# MultiDrop.net
KiCad netlist of a schematic drawn in EAGLE
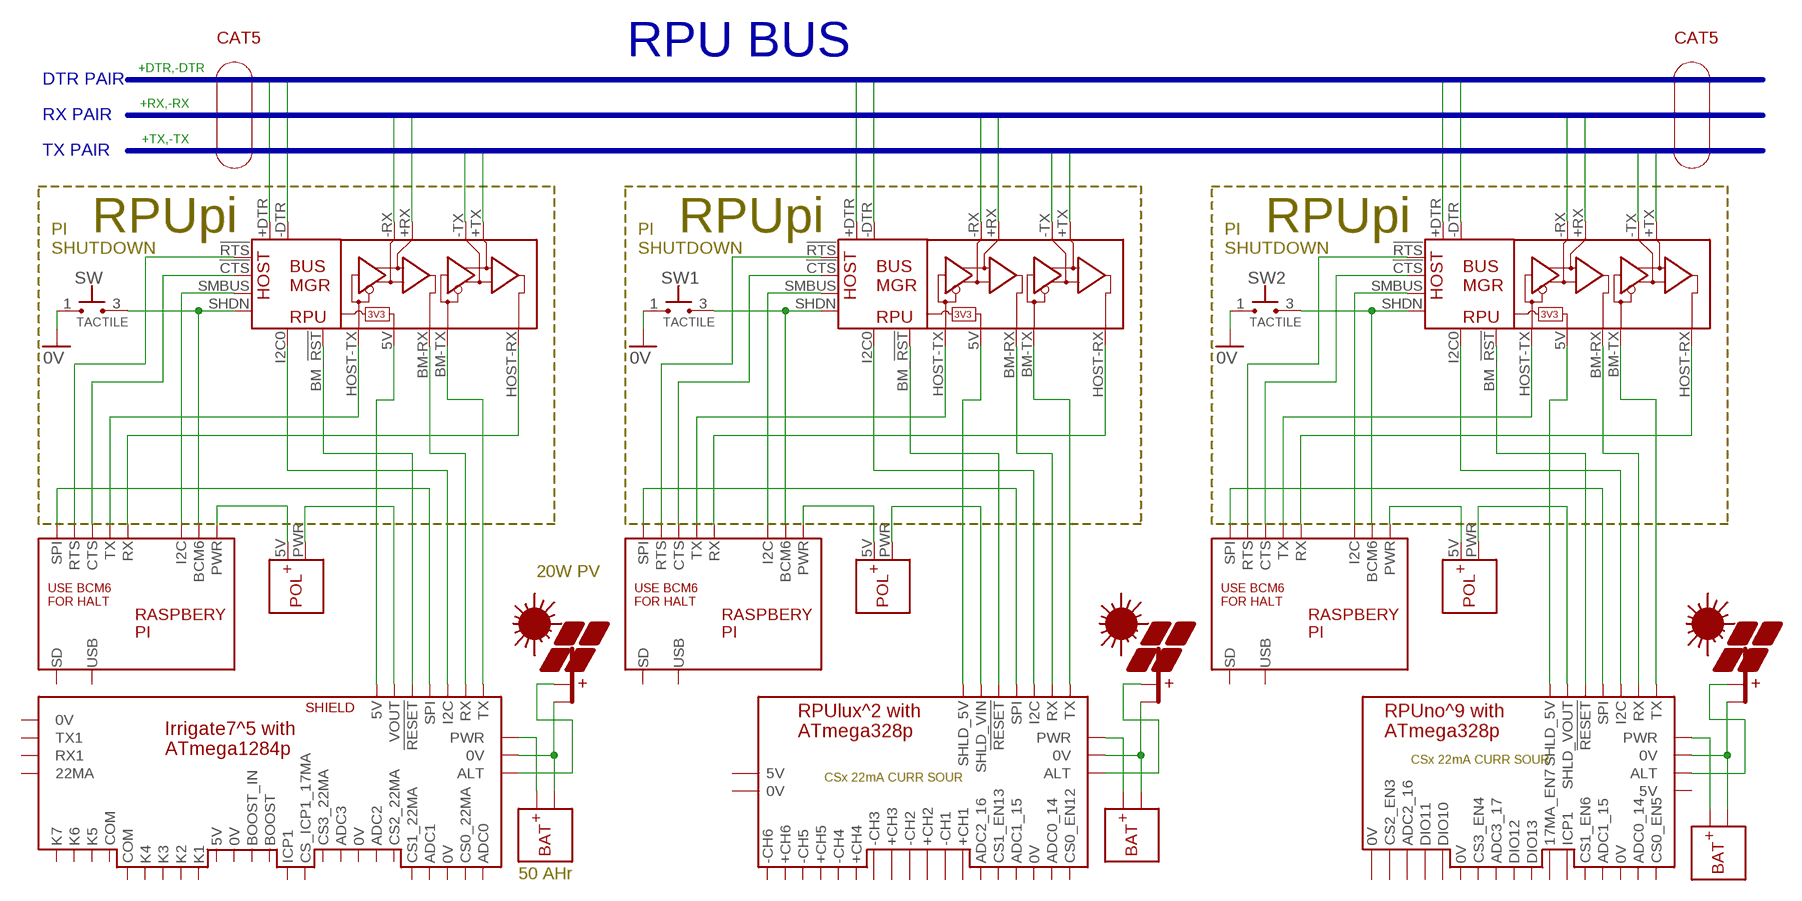
[diagram p0: schematic, sheet 1]

(export (version "E")
  (design (tool "Eeschema 10.0.6"))
  (components
    (comp (ref "BM1")
      (value "RPUNO")
      (footprint "eagle-import:NA-30")
      (libsource (lib "eagle-import") (part "RPUNO"))
    )
    (comp (ref "PV1")
      (value "PV")
      (footprint "eagle-import:NA-30")
      (libsource (lib "eagle-import") (part "PV"))
    )
    (comp (ref "PV2")
      (value "PV")
      (footprint "eagle-import:NA-30")
      (libsource (lib "eagle-import") (part "PV"))
    )
    (comp (ref "PV4")
      (value "PV")
      (footprint "eagle-import:NA-30")
      (libsource (lib "eagle-import") (part "PV"))
    )
    (comp (ref "SW")
      (value "TACTILE")
      (footprint "eagle-import:KS11")
      (libsource (lib "eagle-import") (part "TAC_SW"))
    )
    (comp (ref "SW1")
      (value "TACTILE")
      (footprint "eagle-import:KS11")
      (libsource (lib "eagle-import") (part "TAC_SW"))
    )
    (comp (ref "SW2")
      (value "TACTILE")
      (footprint "eagle-import:KS11")
      (libsource (lib "eagle-import") (part "TAC_SW"))
    )
    (comp (ref "U$1")
      (value "IRRIGATE7")
      (footprint "eagle-import:WITH_RPU_NAMES")
      (libsource (lib "eagle-import") (part "IRRIGATE7"))
    )
    (comp (ref "U$2")
      (value "RPULUX")
      (footprint "eagle-import:WITH_RPU_NAMES")
      (libsource (lib "eagle-import") (part "RPULUX"))
    )
    (comp (ref "U$3")
      (value "BUS_MGR")
      (footprint "eagle-import:WITH_RPU_NAMES")
      (libsource (lib "eagle-import") (part "BUS_MGR"))
    )
    (comp (ref "U$4")
      (value "BAT")
      (footprint "eagle-import:NA-30")
      (libsource (lib "eagle-import") (part "BAT"))
    )
    (comp (ref "U$5")
      (value "PI")
      (footprint "eagle-import:NA-30")
      (libsource (lib "eagle-import") (part "PI"))
    )
    (comp (ref "U$6")
      (value "BUS_MGR")
      (footprint "eagle-import:WITH_RPU_NAMES")
      (libsource (lib "eagle-import") (part "BUS_MGR"))
    )
    (comp (ref "U$7")
      (value "BAT")
      (footprint "eagle-import:NA-30")
      (libsource (lib "eagle-import") (part "BAT"))
    )
    (comp (ref "U$8")
      (value "BUS_MGR")
      (footprint "eagle-import:WITH_RPU_NAMES")
      (libsource (lib "eagle-import") (part "BUS_MGR"))
    )
    (comp (ref "U$9")
      (value "BAT")
      (footprint "eagle-import:NA-30")
      (libsource (lib "eagle-import") (part "BAT"))
    )
    (comp (ref "U$10")
      (value "PI")
      (footprint "eagle-import:NA-30")
      (libsource (lib "eagle-import") (part "PI"))
    )
    (comp (ref "U$11")
      (value "PI")
      (footprint "eagle-import:NA-30")
      (libsource (lib "eagle-import") (part "PI"))
    )
    (comp (ref "U$12")
      (value "POL")
      (footprint "eagle-import:WITH_RPU_NAMES")
      (libsource (lib "eagle-import") (part "POL"))
    )
    (comp (ref "U$13")
      (value "POL")
      (footprint "eagle-import:WITH_RPU_NAMES")
      (libsource (lib "eagle-import") (part "POL"))
    )
    (comp (ref "U$14")
      (value "POL")
      (footprint "eagle-import:WITH_RPU_NAMES")
      (libsource (lib "eagle-import") (part "POL"))
    )
  )
  (nets
    (net (code "10") (name "0V") (class "Default")
      (node (ref "SW") (pin "1") (pinfunction "1_1") (pintype "passive"))
      (node (ref "SW1") (pin "1") (pinfunction "1_1") (pintype "passive"))
      (node (ref "SW2") (pin "1") (pinfunction "1_1") (pintype "passive"))
    )
    (net (code "11") (name "Net-(BM1-ALT)") (class "Default")
      (node (ref "BM1") (pin "20") (pinfunction "ALT_20") (pintype "bidirectional"))
      (node (ref "PV4") (pin "1") (pinfunction "+PV_1") (pintype "bidirectional"))
    )
    (net (code "12") (name "Net-(BM1-I2C)") (class "Default")
      (node (ref "BM1") (pin "3") (pinfunction "I2C_3") (pintype "bidirectional"))
      (node (ref "U$6") (pin "I2C0") (pinfunction "I2C0_I2C0") (pintype "bidirectional"))
    )
    (net (code "13") (name "Net-(BM1-PWR)") (class "Default")
      (node (ref "BM1") (pin "8") (pinfunction "PWR_8") (pintype "bidirectional"))
      (node (ref "U$7") (pin "1") (pinfunction "+BAT_1") (pintype "bidirectional"))
    )
    (net (code "14") (name "Net-(BM1-RX)") (class "Default")
      (node (ref "BM1") (pin "2") (pinfunction "RX_2") (pintype "bidirectional"))
      (node (ref "U$6") (pin "BM-RX") (pinfunction "BM_RX_BM-RX") (pintype "bidirectional"))
    )
    (net (code "15") (name "Net-(BM1-SHLD_5V)") (class "Default")
      (node (ref "BM1") (pin "6") (pinfunction "SHLD_5V_6") (pintype "bidirectional"))
      (node (ref "U$6") (pin "5V") (pinfunction "PWR_5V") (pintype "bidirectional"))
    )
    (net (code "16") (name "Net-(BM1-SHLD_VOUT)") (class "Default")
      (node (ref "BM1") (pin "7") (pinfunction "SHLD_VOUT_7") (pintype "bidirectional"))
      (node (ref "U$14") (pin "PWR") (pinfunction "VIN_PWR") (pintype "bidirectional"))
    )
    (net (code "17") (name "Net-(BM1-SPI)") (class "Default")
      (node (ref "BM1") (pin "4") (pinfunction "SPI_4") (pintype "bidirectional"))
      (node (ref "U$10") (pin "10") (pinfunction "SPI_10") (pintype "bidirectional"))
    )
    (net (code "18") (name "Net-(BM1-TX)") (class "Default")
      (node (ref "BM1") (pin "1") (pinfunction "TX_1") (pintype "bidirectional"))
      (node (ref "U$6") (pin "BM-TX") (pinfunction "BM_TX_BM-TX") (pintype "bidirectional"))
    )
    (net (code "19") (name "Net-(BM1-~{RESET})") (class "Default")
      (node (ref "BM1") (pin "5") (pinfunction "~{RESET}_5") (pintype "bidirectional"))
      (node (ref "U$6") (pin "BM_!RST!") (pinfunction "BM-~{RST}_BM_!RST!") (pintype "bidirectional"))
    )
    (net (code "20") (name "Net-(PV1-+PV)") (class "Default")
      (node (ref "PV1") (pin "1") (pinfunction "+PV_1") (pintype "bidirectional"))
      (node (ref "U$1") (pin "AUX") (pinfunction "ALT_AUX") (pintype "bidirectional"))
    )
    (net (code "21") (name "Net-(PV1--PV)") (class "Default")
      (node (ref "PV1") (pin "2") (pinfunction "-PV_2") (pintype "bidirectional"))
      (node (ref "U$1") (pin "0V@PWR") (pinfunction "0V_0V@PWR") (pintype "bidirectional"))
      (node (ref "U$4") (pin "2") (pinfunction "-BAT_2") (pintype "bidirectional"))
    )
    (net (code "22") (name "Net-(PV2-+PV)") (class "Default")
      (node (ref "PV2") (pin "1") (pinfunction "+PV_1") (pintype "bidirectional"))
      (node (ref "U$2") (pin "AUX") (pinfunction "ALT_AUX") (pintype "bidirectional"))
    )
    (net (code "23") (name "Net-(PV2--PV)") (class "Default")
      (node (ref "PV2") (pin "2") (pinfunction "-PV_2") (pintype "bidirectional"))
      (node (ref "U$2") (pin "0V@PWR") (pinfunction "0V_0V@PWR") (pintype "bidirectional"))
      (node (ref "U$9") (pin "2") (pinfunction "-BAT_2") (pintype "bidirectional"))
    )
    (net (code "24") (name "Net-(PV4--PV)") (class "Default")
      (node (ref "BM1") (pin "9") (pinfunction "0V_9") (pintype "bidirectional"))
      (node (ref "PV4") (pin "2") (pinfunction "-PV_2") (pintype "bidirectional"))
      (node (ref "U$7") (pin "2") (pinfunction "-BAT_2") (pintype "bidirectional"))
    )
    (net (code "25") (name "Net-(U$1-PadI2C)") (class "Default")
      (node (ref "U$1") (pin "I2C") (pinfunction "I2C_I2C") (pintype "bidirectional"))
      (node (ref "U$8") (pin "I2C0") (pinfunction "I2C0_I2C0") (pintype "bidirectional"))
    )
    (net (code "26") (name "Net-(U$1-VOUT)") (class "Default")
      (node (ref "U$1") (pin "SHLD_VOUT") (pinfunction "VOUT_SHLD_VOUT") (pintype "bidirectional"))
      (node (ref "U$12") (pin "PWR") (pinfunction "VIN_PWR") (pintype "bidirectional"))
    )
    (net (code "27") (name "Net-(U$1-~{RESET})") (class "Default")
      (node (ref "U$1") (pin "!RESET") (pinfunction "~{RESET}_!RESET") (pintype "bidirectional"))
      (node (ref "U$8") (pin "BM_!RST!") (pinfunction "BM-~{RST}_BM_!RST!") (pintype "bidirectional"))
    )
    (net (code "28") (name "Net-(U$2-PadI2C)") (class "Default")
      (node (ref "U$2") (pin "I2C") (pinfunction "I2C_I2C") (pintype "bidirectional"))
      (node (ref "U$3") (pin "I2C0") (pinfunction "I2C0_I2C0") (pintype "bidirectional"))
    )
    (net (code "29") (name "Net-(U$2-~{RESET})") (class "Default")
      (node (ref "U$2") (pin "!RESET") (pinfunction "~{RESET}_!RESET") (pintype "bidirectional"))
      (node (ref "U$3") (pin "BM_!RST!") (pinfunction "BM-~{RST}_BM_!RST!") (pintype "bidirectional"))
    )
    (net (code "30") (name "Net-(U$3-BM_RX)") (class "Default")
      (node (ref "U$2") (pin "RX") (pinfunction "RX_RX") (pintype "bidirectional"))
      (node (ref "U$3") (pin "BM-RX") (pinfunction "BM_RX_BM-RX") (pintype "bidirectional"))
    )
    (net (code "31") (name "Net-(U$3-BM_TX)") (class "Default")
      (node (ref "U$2") (pin "TX") (pinfunction "TX_TX") (pintype "bidirectional"))
      (node (ref "U$3") (pin "BM-TX") (pinfunction "BM_TX_BM-TX") (pintype "bidirectional"))
    )
    (net (code "32") (name "Net-(U$3-HOST_RX)") (class "Default")
      (node (ref "U$3") (pin "HOST-RX") (pinfunction "HOST_RX_HOST-RX") (pintype "bidirectional"))
      (node (ref "U$5") (pin "3") (pinfunction "RX_3") (pintype "bidirectional"))
    )
    (net (code "33") (name "Net-(U$3-HOST_TX)") (class "Default")
      (node (ref "U$3") (pin "HOST-TX") (pinfunction "HOST_TX_HOST-TX") (pintype "bidirectional"))
      (node (ref "U$5") (pin "4") (pinfunction "TX_4") (pintype "bidirectional"))
    )
    (net (code "34") (name "Net-(U$3-PWR)") (class "Default")
      (node (ref "U$2") (pin "SHLD_5V") (pinfunction "SHLD_5V_SHLD_5V") (pintype "bidirectional"))
      (node (ref "U$3") (pin "5V") (pinfunction "PWR_5V") (pintype "bidirectional"))
    )
    (net (code "35") (name "Net-(U$3-~{CTS})") (class "Default")
      (node (ref "U$3") (pin "!CTS") (pinfunction "~{CTS}_!CTS") (pintype "bidirectional"))
      (node (ref "U$5") (pin "1") (pinfunction "CTS_1") (pintype "input"))
    )
    (net (code "36") (name "Net-(U$3-~{RTS})") (class "Default")
      (node (ref "U$3") (pin "!RTS") (pinfunction "~{RTS}_!RTS") (pintype "bidirectional"))
      (node (ref "U$5") (pin "2") (pinfunction "RTS_2") (pintype "input"))
    )
    (net (code "37") (name "Net-(U$4-+BAT)") (class "Default")
      (node (ref "U$1") (pin "PWR") (pinfunction "PWR_PWR") (pintype "bidirectional"))
      (node (ref "U$4") (pin "1") (pinfunction "+BAT_1") (pintype "bidirectional"))
    )
    (net (code "38") (name "Net-(U$5-BCM6)") (class "Default")
      (node (ref "SW1") (pin "3") (pinfunction "3_3") (pintype "passive"))
      (node (ref "U$3") (pin "SHDN") (pinfunction "SHDN_SHDN") (pintype "bidirectional"))
      (node (ref "U$5") (pin "7") (pinfunction "BCM6_7") (pintype "bidirectional"))
    )
    (net (code "39") (name "Net-(U$5-I2C)") (class "Default")
      (node (ref "U$3") (pin "SMBUS") (pinfunction "SMBUS_SMBUS") (pintype "bidirectional"))
      (node (ref "U$5") (pin "8") (pinfunction "I2C_8") (pintype "bidirectional"))
    )
    (net (code "40") (name "Net-(U$5-PWR)") (class "Default")
      (node (ref "U$13") (pin "5V") (pinfunction "5V_5V") (pintype "bidirectional"))
      (node (ref "U$5") (pin "12") (pinfunction "PWR_12") (pintype "bidirectional"))
    )
    (net (code "41") (name "Net-(U$5-SPI)") (class "Default")
      (node (ref "U$2") (pin "SPI") (pinfunction "SPI_SPI") (pintype "bidirectional"))
      (node (ref "U$5") (pin "10") (pinfunction "SPI_10") (pintype "bidirectional"))
    )
    (net (code "42") (name "Net-(U$8-BM_RX)") (class "Default")
      (node (ref "U$1") (pin "RX") (pinfunction "RX_RX") (pintype "bidirectional"))
      (node (ref "U$8") (pin "BM-RX") (pinfunction "BM_RX_BM-RX") (pintype "bidirectional"))
    )
    (net (code "43") (name "Net-(U$8-BM_TX)") (class "Default")
      (node (ref "U$1") (pin "TX") (pinfunction "TX_TX") (pintype "bidirectional"))
      (node (ref "U$8") (pin "BM-TX") (pinfunction "BM_TX_BM-TX") (pintype "bidirectional"))
    )
    (net (code "44") (name "Net-(U$8-PWR)") (class "Default")
      (node (ref "U$1") (pin "SHLD_5V") (pinfunction "5V_SHLD_5V") (pintype "bidirectional"))
      (node (ref "U$8") (pin "5V") (pinfunction "PWR_5V") (pintype "bidirectional"))
    )
    (net (code "45") (name "Net-(U$9-+BAT)") (class "Default")
      (node (ref "U$2") (pin "PWR") (pinfunction "PWR_PWR") (pintype "bidirectional"))
      (node (ref "U$9") (pin "1") (pinfunction "+BAT_1") (pintype "bidirectional"))
    )
    (net (code "46") (name "Net-(U$10-BCM6)") (class "Default")
      (node (ref "SW2") (pin "3") (pinfunction "3_3") (pintype "passive"))
      (node (ref "U$10") (pin "7") (pinfunction "BCM6_7") (pintype "bidirectional"))
      (node (ref "U$6") (pin "SHDN") (pinfunction "SHDN_SHDN") (pintype "bidirectional"))
    )
    (net (code "47") (name "Net-(U$10-CTS)") (class "Default")
      (node (ref "U$10") (pin "1") (pinfunction "CTS_1") (pintype "input"))
      (node (ref "U$6") (pin "!CTS") (pinfunction "~{CTS}_!CTS") (pintype "bidirectional"))
    )
    (net (code "48") (name "Net-(U$10-I2C)") (class "Default")
      (node (ref "U$10") (pin "8") (pinfunction "I2C_8") (pintype "bidirectional"))
      (node (ref "U$6") (pin "SMBUS") (pinfunction "SMBUS_SMBUS") (pintype "bidirectional"))
    )
    (net (code "49") (name "Net-(U$10-PWR)") (class "Default")
      (node (ref "U$10") (pin "12") (pinfunction "PWR_12") (pintype "bidirectional"))
      (node (ref "U$14") (pin "5V") (pinfunction "5V_5V") (pintype "bidirectional"))
    )
    (net (code "50") (name "Net-(U$10-RTS)") (class "Default")
      (node (ref "U$10") (pin "2") (pinfunction "RTS_2") (pintype "input"))
      (node (ref "U$6") (pin "!RTS") (pinfunction "~{RTS}_!RTS") (pintype "bidirectional"))
    )
    (net (code "51") (name "Net-(U$10-RX)") (class "Default")
      (node (ref "U$10") (pin "3") (pinfunction "RX_3") (pintype "bidirectional"))
      (node (ref "U$6") (pin "HOST-RX") (pinfunction "HOST_RX_HOST-RX") (pintype "bidirectional"))
    )
    (net (code "52") (name "Net-(U$10-TX)") (class "Default")
      (node (ref "U$10") (pin "4") (pinfunction "TX_4") (pintype "bidirectional"))
      (node (ref "U$6") (pin "HOST-TX") (pinfunction "HOST_TX_HOST-TX") (pintype "bidirectional"))
    )
    (net (code "53") (name "Net-(U$11-BCM6)") (class "Default")
      (node (ref "SW") (pin "3") (pinfunction "3_3") (pintype "passive"))
      (node (ref "U$11") (pin "7") (pinfunction "BCM6_7") (pintype "bidirectional"))
      (node (ref "U$8") (pin "SHDN") (pinfunction "SHDN_SHDN") (pintype "bidirectional"))
    )
    (net (code "54") (name "Net-(U$11-CTS)") (class "Default")
      (node (ref "U$11") (pin "1") (pinfunction "CTS_1") (pintype "input"))
      (node (ref "U$8") (pin "!CTS") (pinfunction "~{CTS}_!CTS") (pintype "bidirectional"))
    )
    (net (code "55") (name "Net-(U$11-I2C)") (class "Default")
      (node (ref "U$11") (pin "8") (pinfunction "I2C_8") (pintype "bidirectional"))
      (node (ref "U$8") (pin "SMBUS") (pinfunction "SMBUS_SMBUS") (pintype "bidirectional"))
    )
    (net (code "56") (name "Net-(U$11-PWR)") (class "Default")
      (node (ref "U$11") (pin "12") (pinfunction "PWR_12") (pintype "bidirectional"))
      (node (ref "U$12") (pin "5V") (pinfunction "5V_5V") (pintype "bidirectional"))
    )
    (net (code "57") (name "Net-(U$11-RTS)") (class "Default")
      (node (ref "U$11") (pin "2") (pinfunction "RTS_2") (pintype "input"))
      (node (ref "U$8") (pin "!RTS") (pinfunction "~{RTS}_!RTS") (pintype "bidirectional"))
    )
    (net (code "58") (name "Net-(U$11-RX)") (class "Default")
      (node (ref "U$11") (pin "3") (pinfunction "RX_3") (pintype "bidirectional"))
      (node (ref "U$8") (pin "HOST-RX") (pinfunction "HOST_RX_HOST-RX") (pintype "bidirectional"))
    )
    (net (code "59") (name "Net-(U$11-SPI)") (class "Default")
      (node (ref "U$1") (pin "SPI") (pinfunction "SPI_SPI") (pintype "bidirectional"))
      (node (ref "U$11") (pin "10") (pinfunction "SPI_10") (pintype "bidirectional"))
    )
    (net (code "60") (name "Net-(U$11-TX)") (class "Default")
      (node (ref "U$11") (pin "4") (pinfunction "TX_4") (pintype "bidirectional"))
      (node (ref "U$8") (pin "HOST-TX") (pinfunction "HOST_TX_HOST-TX") (pintype "bidirectional"))
    )
    (net (code "61") (name "Net-(U$13-VIN)") (class "Default")
      (node (ref "U$13") (pin "PWR") (pinfunction "VIN_PWR") (pintype "bidirectional"))
      (node (ref "U$2") (pin "SHLD_VOUT") (pinfunction "SHLD_VIN_SHLD_VOUT") (pintype "bidirectional"))
    )
    (net (code "62") (name "unconnected-(BM1-0V-Pad26)") (class "Default")
      (node (ref "BM1") (pin "26") (pinfunction "0V_26") (pintype "bidirectional"))
    )
    (net (code "63") (name "unconnected-(BM1-0V-Pad27)") (class "Default")
      (node (ref "BM1") (pin "27") (pinfunction "0V_27") (pintype "bidirectional"))
    )
    (net (code "64") (name "unconnected-(BM1-0V-Pad28)") (class "Default")
      (node (ref "BM1") (pin "28") (pinfunction "0V_28") (pintype "bidirectional"))
    )
    (net (code "65") (name "unconnected-(BM1-5V-Pad19)") (class "Default")
      (node (ref "BM1") (pin "19") (pinfunction "5V_19") (pintype "bidirectional"))
    )
    (net (code "66") (name "unconnected-(BM1-17MA_EN7-Pad21)") (class "Default")
      (node (ref "BM1") (pin "21") (pinfunction "17MA_EN7_21") (pintype "bidirectional"))
    )
    (net (code "67") (name "unconnected-(BM1-ADC0_14-Pad11)") (class "Default")
      (node (ref "BM1") (pin "11") (pinfunction "ADC0_14_11") (pintype "bidirectional"))
    )
    (net (code "68") (name "unconnected-(BM1-ADC1_15-Pad10)") (class "Default")
      (node (ref "BM1") (pin "10") (pinfunction "ADC1_15_10") (pintype "bidirectional"))
    )
    (net (code "69") (name "unconnected-(BM1-ADC2_16-Pad13)") (class "Default")
      (node (ref "BM1") (pin "13") (pinfunction "ADC2_16_13") (pintype "bidirectional"))
    )
    (net (code "70") (name "unconnected-(BM1-ADC3_17-Pad16)") (class "Default")
      (node (ref "BM1") (pin "16") (pinfunction "ADC3_17_16") (pintype "bidirectional"))
    )
    (net (code "71") (name "unconnected-(BM1-CS0_EN5-Pad23)") (class "Default")
      (node (ref "BM1") (pin "23") (pinfunction "CS0_EN5_23") (pintype "bidirectional"))
    )
    (net (code "72") (name "unconnected-(BM1-CS1_EN6-Pad22)") (class "Default")
      (node (ref "BM1") (pin "22") (pinfunction "CS1_EN6_22") (pintype "bidirectional"))
    )
    (net (code "73") (name "unconnected-(BM1-CS2_EN3-Pad24)") (class "Default")
      (node (ref "BM1") (pin "24") (pinfunction "CS2_EN3_24") (pintype "bidirectional"))
    )
    (net (code "74") (name "unconnected-(BM1-CS3_EN4-Pad29)") (class "Default")
      (node (ref "BM1") (pin "29") (pinfunction "CS3_EN4_29") (pintype "bidirectional"))
    )
    (net (code "75") (name "unconnected-(BM1-DIO10-Pad15)") (class "Default")
      (node (ref "BM1") (pin "15") (pinfunction "DIO10_15") (pintype "bidirectional"))
    )
    (net (code "76") (name "unconnected-(BM1-DIO11-Pad14)") (class "Default")
      (node (ref "BM1") (pin "14") (pinfunction "DIO11_14") (pintype "bidirectional"))
    )
    (net (code "77") (name "unconnected-(BM1-DIO12-Pad17)") (class "Default")
      (node (ref "BM1") (pin "17") (pinfunction "DIO12_17") (pintype "bidirectional"))
    )
    (net (code "78") (name "unconnected-(BM1-DIO13-Pad18)") (class "Default")
      (node (ref "BM1") (pin "18") (pinfunction "DIO13_18") (pintype "bidirectional"))
    )
    (net (code "79") (name "unconnected-(BM1-ICP1-Pad12)") (class "Default")
      (node (ref "BM1") (pin "12") (pinfunction "ICP1_12") (pintype "bidirectional"))
    )
    (net (code "80") (name "unconnected-(U$1-0V-Pad0V@ADC2)") (class "Default")
      (node (ref "U$1") (pin "0V@ADC2") (pinfunction "0V_0V@ADC2") (pintype "bidirectional"))
    )
    (net (code "81") (name "unconnected-(U$1-0V-Pad17MA@ICP3)") (class "Default")
      (node (ref "U$1") (pin "17MA@ICP3") (pinfunction "0V_17MA@ICP3") (pintype "bidirectional"))
    )
    (net (code "82") (name "unconnected-(U$1-0V-PadICP3)") (class "Default")
      (node (ref "U$1") (pin "ICP3") (pinfunction "0V_ICP3") (pintype "bidirectional"))
    )
    (net (code "83") (name "unconnected-(U$1-22MA-Pad22MA@DIO2)") (class "Default")
      (node (ref "U$1") (pin "22MA@DIO2") (pinfunction "22MA_22MA@DIO2") (pintype "bidirectional"))
    )
    (net (code "84") (name "unconnected-(U$1-ADC2-PadADC4)") (class "Default")
      (node (ref "U$1") (pin "ADC4") (pinfunction "ADC2_ADC4") (pintype "bidirectional"))
    )
    (net (code "85") (name "unconnected-(U$1-ADC3-PadADC5)") (class "Default")
      (node (ref "U$1") (pin "ADC5") (pinfunction "ADC3_ADC5") (pintype "bidirectional"))
    )
    (net (code "86") (name "unconnected-(U$1-COM-PadCOM@K4)") (class "Default")
      (node (ref "U$1") (pin "COM@K4") (pinfunction "COM_COM@K4") (pintype "bidirectional"))
    )
    (net (code "87") (name "unconnected-(U$1-COM-PadCOM@K5)") (class "Default")
      (node (ref "U$1") (pin "COM@K5") (pinfunction "COM_COM@K5") (pintype "bidirectional"))
    )
    (net (code "88") (name "unconnected-(U$1-CS0_22MA-Pad22MA@ADC0)") (class "Default")
      (node (ref "U$1") (pin "22MA@ADC0") (pinfunction "CS0_22MA_22MA@ADC0") (pintype "bidirectional"))
    )
    (net (code "89") (name "unconnected-(U$1-CS1_22MA-Pad22MA@ADC1)") (class "Default")
      (node (ref "U$1") (pin "22MA@ADC1") (pinfunction "CS1_22MA_22MA@ADC1") (pintype "bidirectional"))
    )
    (net (code "90") (name "unconnected-(U$1-CS2_22MA-Pad22MA@ADC4)") (class "Default")
      (node (ref "U$1") (pin "22MA@ADC4") (pinfunction "CS2_22MA_22MA@ADC4") (pintype "bidirectional"))
    )
    (net (code "91") (name "unconnected-(U$1-CS3_22MA-Pad22MA@ADC5)") (class "Default")
      (node (ref "U$1") (pin "22MA@ADC5") (pinfunction "CS3_22MA_22MA@ADC5") (pintype "bidirectional"))
    )
    (net (code "92") (name "unconnected-(U$1-CS_ICP1_17MA-Pad17MA@ICP1)") (class "Default")
      (node (ref "U$1") (pin "17MA@ICP1") (pinfunction "CS_ICP1_17MA_17MA@ICP1") (pintype "bidirectional"))
    )
    (net (code "93") (name "unconnected-(U$1-Pad0V)") (class "Default")
      (node (ref "U$1") (pin "0V") (pinfunction "0V_0V") (pintype "bidirectional"))
    )
    (net (code "94") (name "unconnected-(U$1-Pad5V)") (class "Default")
      (node (ref "U$1") (pin "5V") (pinfunction "5V_5V") (pintype "bidirectional"))
    )
    (net (code "95") (name "unconnected-(U$1-PadADC0)") (class "Default")
      (node (ref "U$1") (pin "ADC0") (pinfunction "ADC0_ADC0") (pintype "bidirectional"))
    )
    (net (code "96") (name "unconnected-(U$1-PadADC1)") (class "Default")
      (node (ref "U$1") (pin "ADC1") (pinfunction "ADC1_ADC1") (pintype "bidirectional"))
    )
    (net (code "97") (name "unconnected-(U$1-PadBOOST)") (class "Default")
      (node (ref "U$1") (pin "BOOST") (pinfunction "BOOST_BOOST") (pintype "bidirectional"))
    )
    (net (code "98") (name "unconnected-(U$1-PadBOOST_IN)") (class "Default")
      (node (ref "U$1") (pin "BOOST_IN") (pinfunction "BOOST_IN_BOOST_IN") (pintype "bidirectional"))
    )
    (net (code "99") (name "unconnected-(U$1-PadICP1)") (class "Default")
      (node (ref "U$1") (pin "ICP1") (pinfunction "ICP1_ICP1") (pintype "bidirectional"))
    )
    (net (code "100") (name "unconnected-(U$1-PadK1)") (class "Default")
      (node (ref "U$1") (pin "K1") (pinfunction "K1_K1") (pintype "bidirectional"))
    )
    (net (code "101") (name "unconnected-(U$1-PadK2)") (class "Default")
      (node (ref "U$1") (pin "K2") (pinfunction "K2_K2") (pintype "bidirectional"))
    )
    (net (code "102") (name "unconnected-(U$1-PadK3)") (class "Default")
      (node (ref "U$1") (pin "K3") (pinfunction "K3_K3") (pintype "bidirectional"))
    )
    (net (code "103") (name "unconnected-(U$1-PadK4)") (class "Default")
      (node (ref "U$1") (pin "K4") (pinfunction "K4_K4") (pintype "bidirectional"))
    )
    (net (code "104") (name "unconnected-(U$1-PadK5)") (class "Default")
      (node (ref "U$1") (pin "K5") (pinfunction "K5_K5") (pintype "bidirectional"))
    )
    (net (code "105") (name "unconnected-(U$1-PadK6)") (class "Default")
      (node (ref "U$1") (pin "K6") (pinfunction "K6_K6") (pintype "bidirectional"))
    )
    (net (code "106") (name "unconnected-(U$1-PadK7)") (class "Default")
      (node (ref "U$1") (pin "K7") (pinfunction "K7_K7") (pintype "bidirectional"))
    )
    (net (code "107") (name "unconnected-(U$1-RX1-PadDIO2)") (class "Default")
      (node (ref "U$1") (pin "DIO2") (pinfunction "RX1_DIO2") (pintype "bidirectional"))
    )
    (net (code "108") (name "unconnected-(U$1-TX1-PadDIO3)") (class "Default")
      (node (ref "U$1") (pin "DIO3") (pinfunction "TX1_DIO3") (pintype "bidirectional"))
    )
    (net (code "109") (name "unconnected-(U$2-0V-Pad0V@DIO2)") (class "Default")
      (node (ref "U$2") (pin "0V@DIO2") (pinfunction "0V_0V@DIO2") (pintype "bidirectional"))
    )
    (net (code "110") (name "unconnected-(U$2-ADC0_14-PadADC0)") (class "Default")
      (node (ref "U$2") (pin "ADC0") (pinfunction "ADC0_14_ADC0") (pintype "bidirectional"))
    )
    (net (code "111") (name "unconnected-(U$2-ADC1_15-PadADC1)") (class "Default")
      (node (ref "U$2") (pin "ADC1") (pinfunction "ADC1_15_ADC1") (pintype "bidirectional"))
    )
    (net (code "112") (name "unconnected-(U$2-ADC2_16-PadADC2)") (class "Default")
      (node (ref "U$2") (pin "ADC2") (pinfunction "ADC2_16_ADC2") (pintype "bidirectional"))
    )
    (net (code "113") (name "unconnected-(U$2-CS0_EN12-Pad22MA@ADC0)") (class "Default")
      (node (ref "U$2") (pin "22MA@ADC0") (pinfunction "CS0_EN12_22MA@ADC0") (pintype "bidirectional"))
    )
    (net (code "114") (name "unconnected-(U$2-CS1_EN13-Pad22MA@ADC1)") (class "Default")
      (node (ref "U$2") (pin "22MA@ADC1") (pinfunction "CS1_EN13_22MA@ADC1") (pintype "bidirectional"))
    )
    (net (code "115") (name "unconnected-(U$2-Pad+CH1)") (class "Default")
      (node (ref "U$2") (pin "+CH1") (pinfunction "+CH1_+CH1") (pintype "bidirectional"))
    )
    (net (code "116") (name "unconnected-(U$2-Pad+CH2)") (class "Default")
      (node (ref "U$2") (pin "+CH2") (pinfunction "+CH2_+CH2") (pintype "bidirectional"))
    )
    (net (code "117") (name "unconnected-(U$2-Pad+CH3)") (class "Default")
      (node (ref "U$2") (pin "+CH3") (pinfunction "+CH3_+CH3") (pintype "bidirectional"))
    )
    (net (code "118") (name "unconnected-(U$2-Pad+CH4)") (class "Default")
      (node (ref "U$2") (pin "+CH4") (pinfunction "+CH4_+CH4") (pintype "bidirectional"))
    )
    (net (code "119") (name "unconnected-(U$2-Pad+CH5)") (class "Default")
      (node (ref "U$2") (pin "+CH5") (pinfunction "+CH5_+CH5") (pintype "bidirectional"))
    )
    (net (code "120") (name "unconnected-(U$2-Pad+CH6)") (class "Default")
      (node (ref "U$2") (pin "+CH6") (pinfunction "+CH6_+CH6") (pintype "bidirectional"))
    )
    (net (code "121") (name "unconnected-(U$2-Pad-CH1)") (class "Default")
      (node (ref "U$2") (pin "-CH1") (pinfunction "-CH1_-CH1") (pintype "bidirectional"))
    )
    (net (code "122") (name "unconnected-(U$2-Pad-CH2)") (class "Default")
      (node (ref "U$2") (pin "-CH2") (pinfunction "-CH2_-CH2") (pintype "bidirectional"))
    )
    (net (code "123") (name "unconnected-(U$2-Pad-CH3)") (class "Default")
      (node (ref "U$2") (pin "-CH3") (pinfunction "-CH3_-CH3") (pintype "bidirectional"))
    )
    (net (code "124") (name "unconnected-(U$2-Pad-CH4)") (class "Default")
      (node (ref "U$2") (pin "-CH4") (pinfunction "-CH4_-CH4") (pintype "bidirectional"))
    )
    (net (code "125") (name "unconnected-(U$2-Pad-CH5)") (class "Default")
      (node (ref "U$2") (pin "-CH5") (pinfunction "-CH5_-CH5") (pintype "bidirectional"))
    )
    (net (code "126") (name "unconnected-(U$2-Pad-CH6)") (class "Default")
      (node (ref "U$2") (pin "-CH6") (pinfunction "-CH6_-CH6") (pintype "bidirectional"))
    )
    (net (code "127") (name "unconnected-(U$2-Pad0V)") (class "Default")
      (node (ref "U$2") (pin "0V") (pinfunction "0V_0V") (pintype "bidirectional"))
    )
    (net (code "128") (name "unconnected-(U$2-Pad5V)") (class "Default")
      (node (ref "U$2") (pin "5V") (pinfunction "5V_5V") (pintype "bidirectional"))
    )
    (net (code "129") (name "unconnected-(U$3-Pad+DTR)") (class "Default")
      (node (ref "U$3") (pin "+DTR") (pinfunction "+DTR_+DTR") (pintype "bidirectional"))
    )
    (net (code "130") (name "unconnected-(U$3-Pad+RX)") (class "Default")
      (node (ref "U$3") (pin "+RX") (pinfunction "+RX_+RX") (pintype "bidirectional"))
    )
    (net (code "131") (name "unconnected-(U$3-Pad+TX)") (class "Default")
      (node (ref "U$3") (pin "+TX") (pinfunction "+TX_+TX") (pintype "bidirectional"))
    )
    (net (code "132") (name "unconnected-(U$3-Pad-DTR)") (class "Default")
      (node (ref "U$3") (pin "-DTR") (pinfunction "-DTR_-DTR") (pintype "bidirectional"))
    )
    (net (code "133") (name "unconnected-(U$3-Pad-RX)") (class "Default")
      (node (ref "U$3") (pin "-RX") (pinfunction "-RX_-RX") (pintype "bidirectional"))
    )
    (net (code "134") (name "unconnected-(U$3-Pad-TX)") (class "Default")
      (node (ref "U$3") (pin "-TX") (pinfunction "-TX_-TX") (pintype "bidirectional"))
    )
    (net (code "135") (name "unconnected-(U$5-SD-Pad9)") (class "Default")
      (node (ref "U$5") (pin "9") (pinfunction "SD_9") (pintype "input"))
    )
    (net (code "136") (name "unconnected-(U$5-USB-Pad11)") (class "Default")
      (node (ref "U$5") (pin "11") (pinfunction "USB_11") (pintype "input"))
    )
    (net (code "137") (name "unconnected-(U$6-Pad+DTR)") (class "Default")
      (node (ref "U$6") (pin "+DTR") (pinfunction "+DTR_+DTR") (pintype "bidirectional"))
    )
    (net (code "138") (name "unconnected-(U$6-Pad+RX)") (class "Default")
      (node (ref "U$6") (pin "+RX") (pinfunction "+RX_+RX") (pintype "bidirectional"))
    )
    (net (code "139") (name "unconnected-(U$6-Pad+TX)") (class "Default")
      (node (ref "U$6") (pin "+TX") (pinfunction "+TX_+TX") (pintype "bidirectional"))
    )
    (net (code "140") (name "unconnected-(U$6-Pad-DTR)") (class "Default")
      (node (ref "U$6") (pin "-DTR") (pinfunction "-DTR_-DTR") (pintype "bidirectional"))
    )
    (net (code "141") (name "unconnected-(U$6-Pad-RX)") (class "Default")
      (node (ref "U$6") (pin "-RX") (pinfunction "-RX_-RX") (pintype "bidirectional"))
    )
    (net (code "142") (name "unconnected-(U$6-Pad-TX)") (class "Default")
      (node (ref "U$6") (pin "-TX") (pinfunction "-TX_-TX") (pintype "bidirectional"))
    )
    (net (code "143") (name "unconnected-(U$8-Pad+DTR)") (class "Default")
      (node (ref "U$8") (pin "+DTR") (pinfunction "+DTR_+DTR") (pintype "bidirectional"))
    )
    (net (code "144") (name "unconnected-(U$8-Pad+RX)") (class "Default")
      (node (ref "U$8") (pin "+RX") (pinfunction "+RX_+RX") (pintype "bidirectional"))
    )
    (net (code "145") (name "unconnected-(U$8-Pad+TX)") (class "Default")
      (node (ref "U$8") (pin "+TX") (pinfunction "+TX_+TX") (pintype "bidirectional"))
    )
    (net (code "146") (name "unconnected-(U$8-Pad-DTR)") (class "Default")
      (node (ref "U$8") (pin "-DTR") (pinfunction "-DTR_-DTR") (pintype "bidirectional"))
    )
    (net (code "147") (name "unconnected-(U$8-Pad-RX)") (class "Default")
      (node (ref "U$8") (pin "-RX") (pinfunction "-RX_-RX") (pintype "bidirectional"))
    )
    (net (code "148") (name "unconnected-(U$8-Pad-TX)") (class "Default")
      (node (ref "U$8") (pin "-TX") (pinfunction "-TX_-TX") (pintype "bidirectional"))
    )
    (net (code "149") (name "unconnected-(U$10-SD-Pad9)") (class "Default")
      (node (ref "U$10") (pin "9") (pinfunction "SD_9") (pintype "input"))
    )
    (net (code "150") (name "unconnected-(U$10-USB-Pad11)") (class "Default")
      (node (ref "U$10") (pin "11") (pinfunction "USB_11") (pintype "input"))
    )
    (net (code "151") (name "unconnected-(U$11-SD-Pad9)") (class "Default")
      (node (ref "U$11") (pin "9") (pinfunction "SD_9") (pintype "input"))
    )
    (net (code "152") (name "unconnected-(U$11-USB-Pad11)") (class "Default")
      (node (ref "U$11") (pin "11") (pinfunction "USB_11") (pintype "input"))
    )
  )
)
